# Programmer_Board.net
KiCad netlist of a schematic drawn in EAGLE
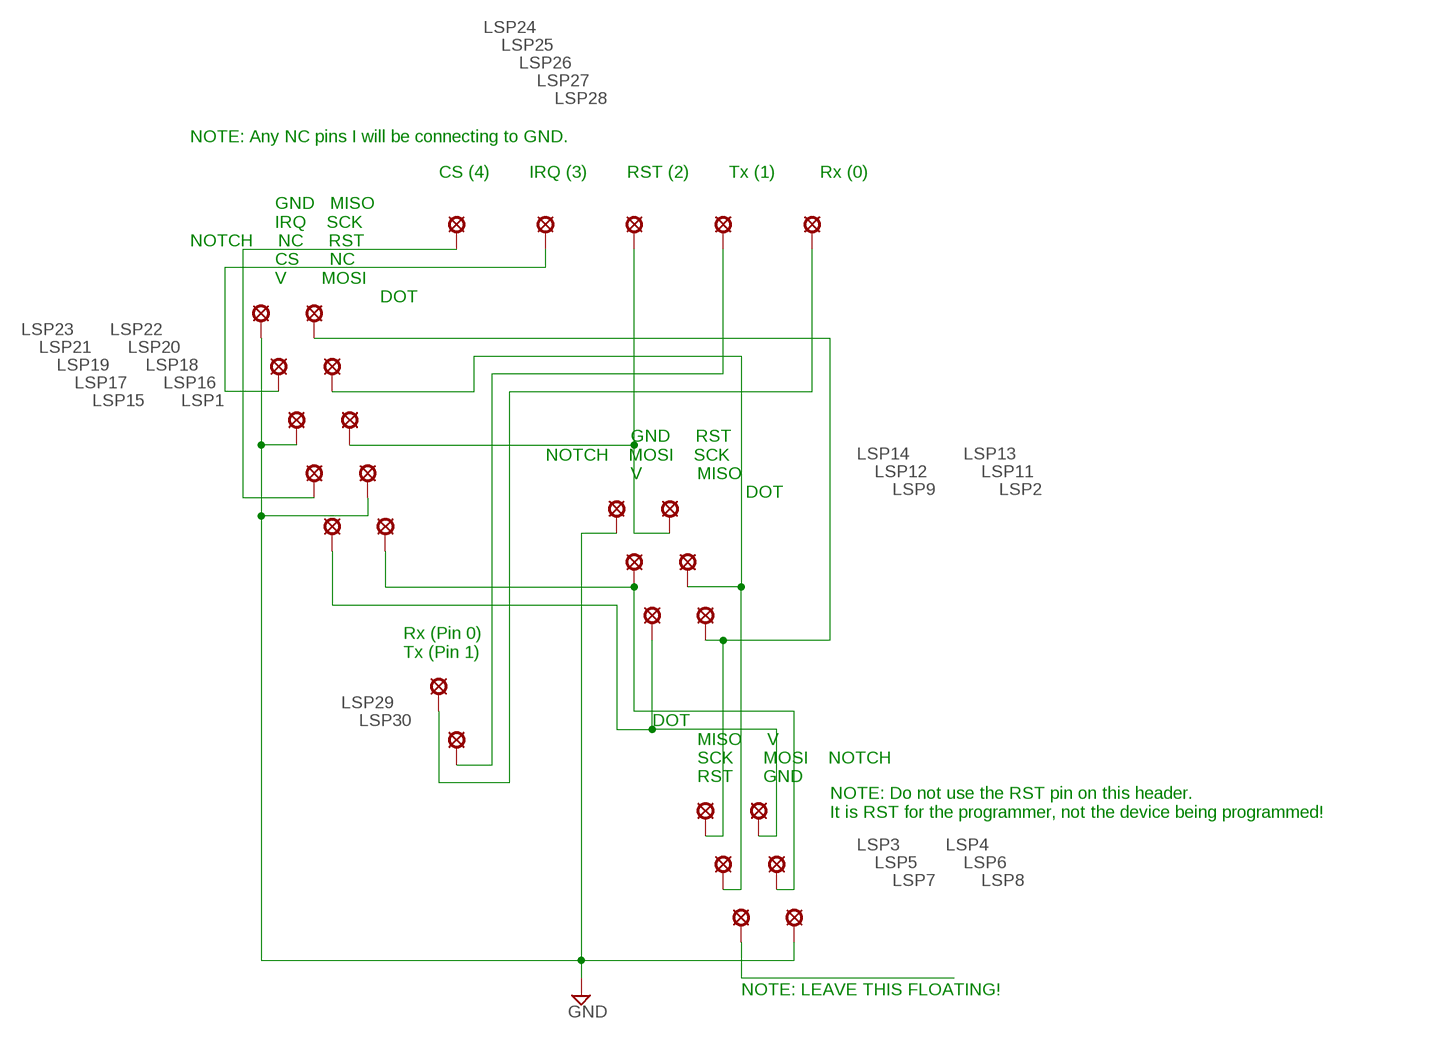
[diagram p0: schematic, sheet 1]

(export (version "E")
  (design (tool "Eeschema 10.0.6"))
  (components
    (comp (ref "LSP1")
      (value "LSP10_S")
      (footprint "eagle-import:LSP10_S")
      (libsource (lib "eagle-import") (part "LSP10_S"))
    )
    (comp (ref "LSP2")
      (value "LSP10_S")
      (footprint "eagle-import:LSP10_S")
      (libsource (lib "eagle-import") (part "LSP10_S"))
    )
    (comp (ref "LSP3")
      (value "LSP10_S")
      (footprint "eagle-import:LSP10_S")
      (libsource (lib "eagle-import") (part "LSP10_S"))
    )
    (comp (ref "LSP4")
      (value "LSP10_CLSP10_C")
      (footprint "eagle-import:LSP10_C")
      (libsource (lib "eagle-import") (part "LSP10_CLSP10_C"))
    )
    (comp (ref "LSP5")
      (value "LSP10_CLSP10_C")
      (footprint "eagle-import:LSP10_C")
      (libsource (lib "eagle-import") (part "LSP10_CLSP10_C"))
    )
    (comp (ref "LSP6")
      (value "LSP10_CLSP10_C")
      (footprint "eagle-import:LSP10_C")
      (libsource (lib "eagle-import") (part "LSP10_CLSP10_C"))
    )
    (comp (ref "LSP7")
      (value "LSP10_CLSP10_C")
      (footprint "eagle-import:LSP10_C")
      (libsource (lib "eagle-import") (part "LSP10_CLSP10_C"))
    )
    (comp (ref "LSP8")
      (value "LSP10_CLSP10_C")
      (footprint "eagle-import:LSP10_C")
      (libsource (lib "eagle-import") (part "LSP10_CLSP10_C"))
    )
    (comp (ref "LSP9")
      (value "LSP10_CLSP10_C")
      (footprint "eagle-import:LSP10_C")
      (libsource (lib "eagle-import") (part "LSP10_CLSP10_C"))
    )
    (comp (ref "LSP11")
      (value "LSP10_CLSP10_C")
      (footprint "eagle-import:LSP10_C")
      (libsource (lib "eagle-import") (part "LSP10_CLSP10_C"))
    )
    (comp (ref "LSP12")
      (value "LSP10_CLSP10_C")
      (footprint "eagle-import:LSP10_C")
      (libsource (lib "eagle-import") (part "LSP10_CLSP10_C"))
    )
    (comp (ref "LSP13")
      (value "LSP10_CLSP10_C")
      (footprint "eagle-import:LSP10_C")
      (libsource (lib "eagle-import") (part "LSP10_CLSP10_C"))
    )
    (comp (ref "LSP14")
      (value "LSP10_CLSP10_C")
      (footprint "eagle-import:LSP10_C")
      (libsource (lib "eagle-import") (part "LSP10_CLSP10_C"))
    )
    (comp (ref "LSP15")
      (value "LSP10_CLSP10_C")
      (footprint "eagle-import:LSP10_C")
      (libsource (lib "eagle-import") (part "LSP10_CLSP10_C"))
    )
    (comp (ref "LSP16")
      (value "LSP10_CLSP10_C")
      (footprint "eagle-import:LSP10_C")
      (libsource (lib "eagle-import") (part "LSP10_CLSP10_C"))
    )
    (comp (ref "LSP17")
      (value "LSP10_CLSP10_C")
      (footprint "eagle-import:LSP10_C")
      (libsource (lib "eagle-import") (part "LSP10_CLSP10_C"))
    )
    (comp (ref "LSP18")
      (value "LSP10_CLSP10_C")
      (footprint "eagle-import:LSP10_C")
      (libsource (lib "eagle-import") (part "LSP10_CLSP10_C"))
    )
    (comp (ref "LSP19")
      (value "LSP10_CLSP10_C")
      (footprint "eagle-import:LSP10_C")
      (libsource (lib "eagle-import") (part "LSP10_CLSP10_C"))
    )
    (comp (ref "LSP20")
      (value "LSP10_CLSP10_C")
      (footprint "eagle-import:LSP10_C")
      (libsource (lib "eagle-import") (part "LSP10_CLSP10_C"))
    )
    (comp (ref "LSP21")
      (value "LSP10_CLSP10_C")
      (footprint "eagle-import:LSP10_C")
      (libsource (lib "eagle-import") (part "LSP10_CLSP10_C"))
    )
    (comp (ref "LSP22")
      (value "LSP10_CLSP10_C")
      (footprint "eagle-import:LSP10_C")
      (libsource (lib "eagle-import") (part "LSP10_CLSP10_C"))
    )
    (comp (ref "LSP23")
      (value "LSP10_CLSP10_C")
      (footprint "eagle-import:LSP10_C")
      (libsource (lib "eagle-import") (part "LSP10_CLSP10_C"))
    )
    (comp (ref "LSP24")
      (value "LSP10_CLSP10_C")
      (footprint "eagle-import:LSP10_C")
      (libsource (lib "eagle-import") (part "LSP10_CLSP10_C"))
    )
    (comp (ref "LSP25")
      (value "LSP10_CLSP10_C")
      (footprint "eagle-import:LSP10_C")
      (libsource (lib "eagle-import") (part "LSP10_CLSP10_C"))
    )
    (comp (ref "LSP26")
      (value "LSP10_CLSP10_C")
      (footprint "eagle-import:LSP10_C")
      (libsource (lib "eagle-import") (part "LSP10_CLSP10_C"))
    )
    (comp (ref "LSP27")
      (value "LSP10_CLSP10_C")
      (footprint "eagle-import:LSP10_C")
      (libsource (lib "eagle-import") (part "LSP10_CLSP10_C"))
    )
    (comp (ref "LSP28")
      (value "LSP10_S")
      (footprint "eagle-import:LSP10_S")
      (libsource (lib "eagle-import") (part "LSP10_S"))
    )
    (comp (ref "LSP29")
      (value "LSP10_S")
      (footprint "eagle-import:LSP10_S")
      (libsource (lib "eagle-import") (part "LSP10_S"))
    )
    (comp (ref "LSP30")
      (value "LSP10_CLSP10_C")
      (footprint "eagle-import:LSP10_C")
      (libsource (lib "eagle-import") (part "LSP10_CLSP10_C"))
    )
  )
  (nets
    (net (code "1") (name "GND") (class "Default")
      (node (ref "LSP14") (pin "P$1") (pinfunction "MP_P$1") (pintype "passive"))
      (node (ref "LSP16") (pin "P$1") (pinfunction "MP_P$1") (pintype "passive"))
      (node (ref "LSP19") (pin "P$1") (pinfunction "MP_P$1") (pintype "passive"))
      (node (ref "LSP23") (pin "P$1") (pinfunction "MP_P$1") (pintype "passive"))
      (node (ref "LSP8") (pin "P$1") (pinfunction "MP_P$1") (pintype "passive"))
    )
    (net (code "2") (name "Net-(LSP1-MP)") (class "Default")
      (node (ref "LSP1") (pin "P$1") (pinfunction "MP_P$1") (pintype "passive"))
      (node (ref "LSP12") (pin "P$1") (pinfunction "MP_P$1") (pintype "passive"))
      (node (ref "LSP6") (pin "P$1") (pinfunction "MP_P$1") (pintype "passive"))
    )
    (net (code "3") (name "Net-(LSP2-MP)") (class "Default")
      (node (ref "LSP2") (pin "P$1") (pinfunction "MP_P$1") (pintype "passive"))
      (node (ref "LSP22") (pin "P$1") (pinfunction "MP_P$1") (pintype "passive"))
      (node (ref "LSP3") (pin "P$1") (pinfunction "MP_P$1") (pintype "passive"))
    )
    (net (code "4") (name "Net-(LSP11-MP)") (class "Default")
      (node (ref "LSP11") (pin "P$1") (pinfunction "MP_P$1") (pintype "passive"))
      (node (ref "LSP20") (pin "P$1") (pinfunction "MP_P$1") (pintype "passive"))
      (node (ref "LSP5") (pin "P$1") (pinfunction "MP_P$1") (pintype "passive"))
    )
    (net (code "5") (name "Net-(LSP13-MP)") (class "Default")
      (node (ref "LSP13") (pin "P$1") (pinfunction "MP_P$1") (pintype "passive"))
      (node (ref "LSP18") (pin "P$1") (pinfunction "MP_P$1") (pintype "passive"))
      (node (ref "LSP26") (pin "P$1") (pinfunction "MP_P$1") (pintype "passive"))
    )
    (net (code "6") (name "Net-(LSP15-MP)") (class "Default")
      (node (ref "LSP15") (pin "P$1") (pinfunction "MP_P$1") (pintype "passive"))
      (node (ref "LSP4") (pin "P$1") (pinfunction "MP_P$1") (pintype "passive"))
      (node (ref "LSP9") (pin "P$1") (pinfunction "MP_P$1") (pintype "passive"))
    )
    (net (code "7") (name "Net-(LSP17-MP)") (class "Default")
      (node (ref "LSP17") (pin "P$1") (pinfunction "MP_P$1") (pintype "passive"))
      (node (ref "LSP24") (pin "P$1") (pinfunction "MP_P$1") (pintype "passive"))
    )
    (net (code "8") (name "Net-(LSP21-MP)") (class "Default")
      (node (ref "LSP21") (pin "P$1") (pinfunction "MP_P$1") (pintype "passive"))
      (node (ref "LSP25") (pin "P$1") (pinfunction "MP_P$1") (pintype "passive"))
    )
    (net (code "9") (name "Net-(LSP27-MP)") (class "Default")
      (node (ref "LSP27") (pin "P$1") (pinfunction "MP_P$1") (pintype "passive"))
      (node (ref "LSP30") (pin "P$1") (pinfunction "MP_P$1") (pintype "passive"))
    )
    (net (code "10") (name "Net-(LSP28-MP)") (class "Default")
      (node (ref "LSP28") (pin "P$1") (pinfunction "MP_P$1") (pintype "passive"))
      (node (ref "LSP29") (pin "P$1") (pinfunction "MP_P$1") (pintype "passive"))
    )
    (net (code "11") (name "unconnected-(LSP7-MP-PadP$1)") (class "Default")
      (node (ref "LSP7") (pin "P$1") (pinfunction "MP_P$1") (pintype "passive"))
    )
  )
)
